# 20190105_ORIGAMI_V1-H-08slot-fixed.net
KiCad netlist of a schematic drawn in EAGLE
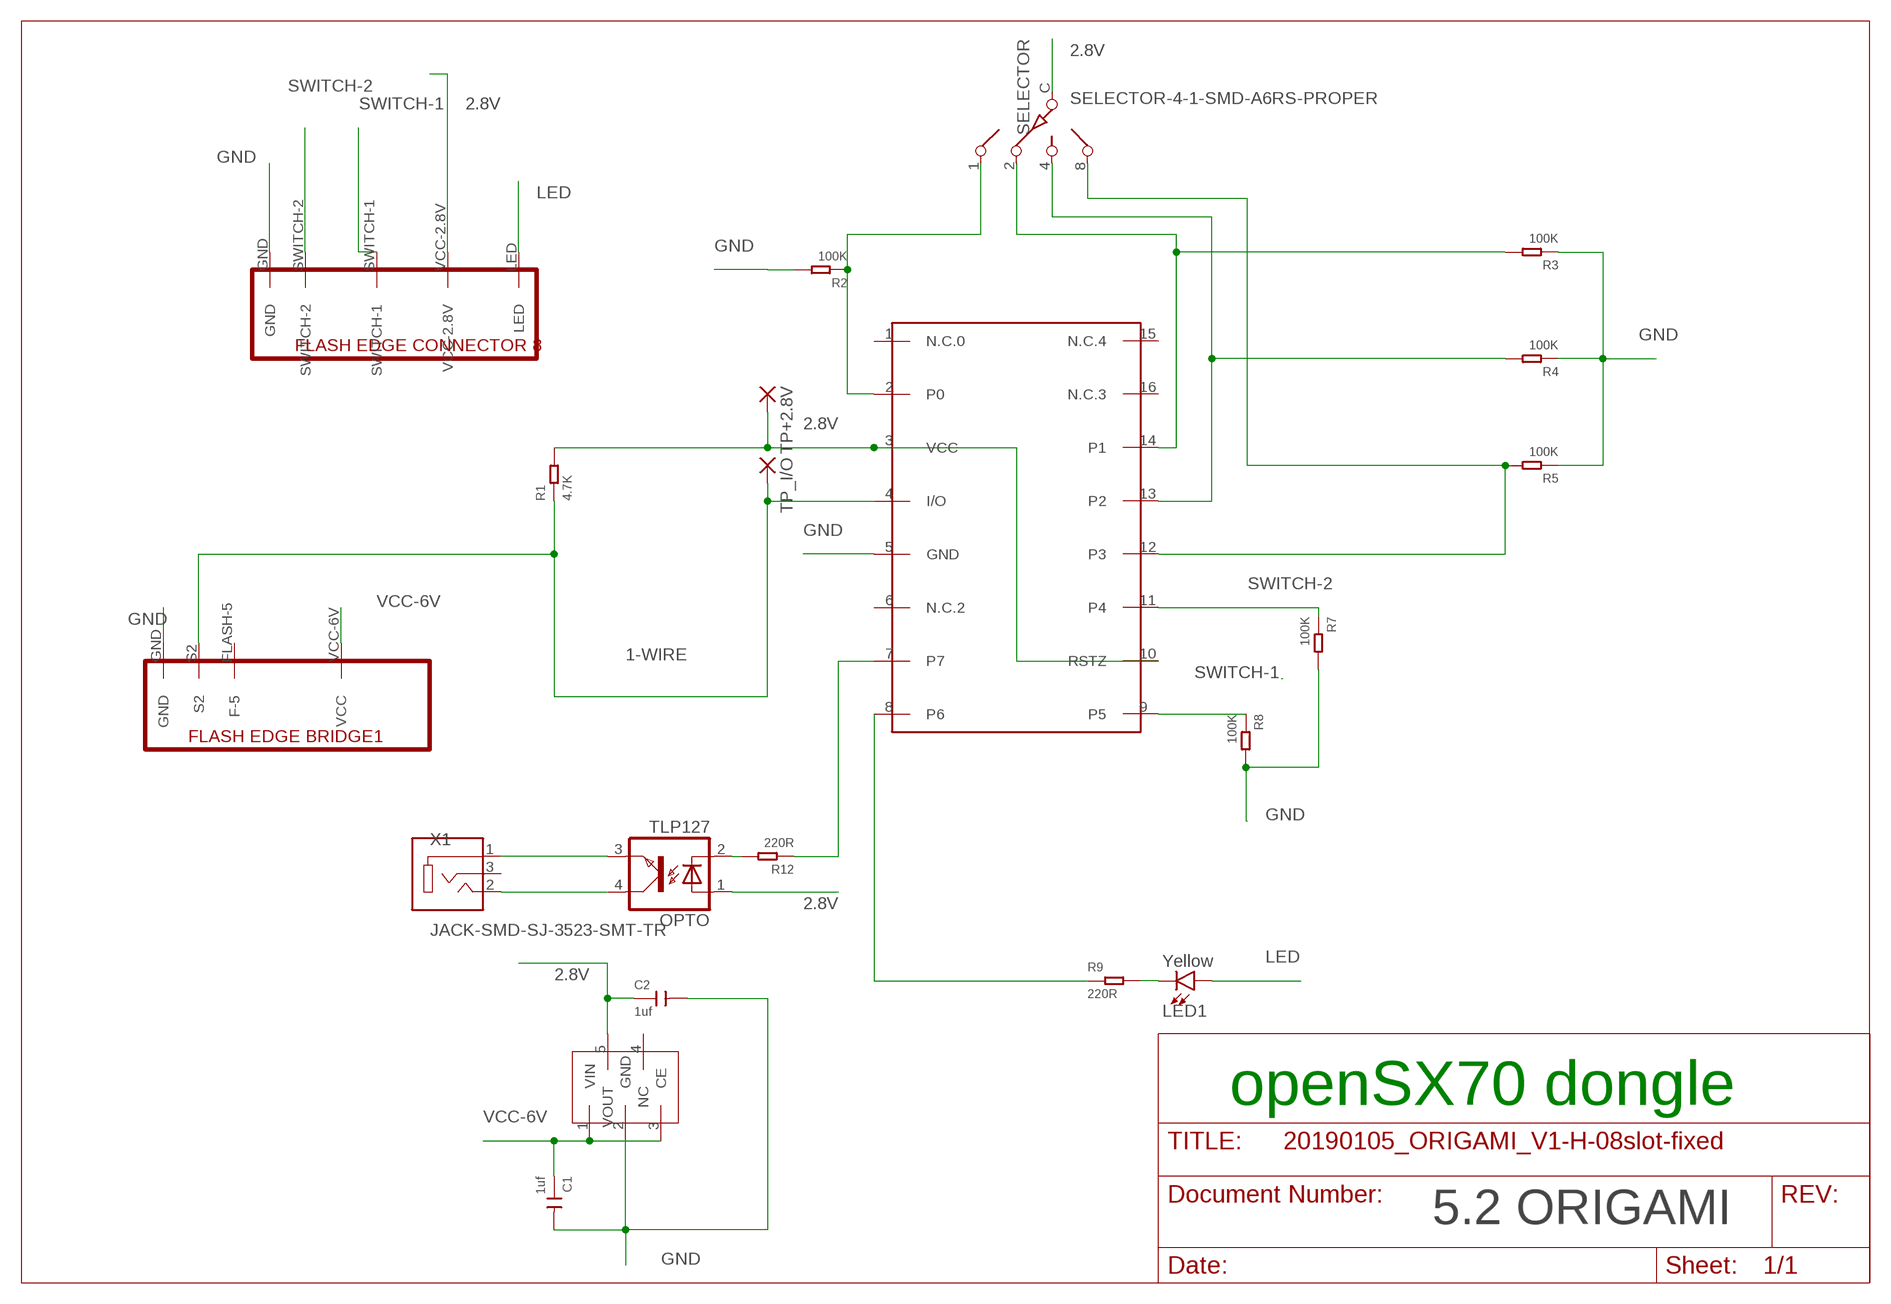
[diagram p0: schematic, sheet 1]

(export (version "E")
  (design (tool "Eeschema 10.0.6"))
  (components
    (comp (ref "C1")
      (value "1uf")
      (footprint "eagle-import:C0603")
      (fields (field (name "MPN") "CC0603KRX7R8BB105"))
      (libsource (lib "eagle-import") (part "CERAMIC-1UF-25V-10%-X7R(0603)"))
    )
    (comp (ref "C2")
      (value "1uf")
      (footprint "eagle-import:C0603")
      (fields (field (name "MPN") "CC0603KRX7R8BB105"))
      (libsource (lib "eagle-import") (part "CERAMIC-1UF-25V-10%-X7R(0603)"))
    )
    (comp (ref "DS2408")
      (value "DS2408")
      (footprint "eagle-import:SO16")
      (libsource (lib "eagle-import") (part "DS2408"))
    )
    (comp (ref "LED1")
      (value "Yellow")
      (footprint "eagle-import:LED-1206")
      (libsource (lib "eagle-import") (part "LED-YELLOWLILYPAD"))
    )
    (comp (ref "OPTO")
      (value "TLP127")
      (footprint "eagle-import:SO-4")
      (libsource (lib "eagle-import") (part "TLP127"))
    )
    (comp (ref "R1")
      (value "4.7K")
      (footprint "eagle-import:R0603")
      (fields (field (name "MPN") "RC0603JR-074K7L"))
      (libsource (lib "eagle-import") (part "SMD-RES-4.7K-5%-1/10W(0603)"))
    )
    (comp (ref "R2")
      (value "100K")
      (footprint "eagle-import:R0603")
      (fields (field (name "MPN") "RC0603FR-07100KL"))
      (libsource (lib "eagle-import") (part "SMD-RES-100K-1%-1/10W(0603)"))
    )
    (comp (ref "R3")
      (value "100K")
      (footprint "eagle-import:R0603")
      (fields (field (name "MPN") "RC0603FR-07100KL"))
      (libsource (lib "eagle-import") (part "SMD-RES-100K-1%-1/10W(0603)"))
    )
    (comp (ref "R4")
      (value "100K")
      (footprint "eagle-import:R0603")
      (fields (field (name "MPN") "RC0603FR-07100KL"))
      (libsource (lib "eagle-import") (part "SMD-RES-100K-1%-1/10W(0603)"))
    )
    (comp (ref "R5")
      (value "100K")
      (footprint "eagle-import:R0603")
      (fields (field (name "MPN") "RC0603FR-07100KL"))
      (libsource (lib "eagle-import") (part "SMD-RES-100K-1%-1/10W(0603)"))
    )
    (comp (ref "R7")
      (value "100K")
      (footprint "eagle-import:R0603")
      (fields (field (name "MPN") "RC0603FR-07100KL"))
      (libsource (lib "eagle-import") (part "SMD-RES-100K-1%-1/10W(0603)"))
    )
    (comp (ref "R8")
      (value "100K")
      (footprint "eagle-import:R0603")
      (fields (field (name "MPN") "RC0603FR-07100KL"))
      (libsource (lib "eagle-import") (part "SMD-RES-100K-1%-1/10W(0603)"))
    )
    (comp (ref "R9")
      (value "220R")
      (footprint "eagle-import:R0603")
      (fields (field (name "MPN") "RC0603JR-07220RL"))
      (libsource (lib "eagle-import") (part "SMD-RES-220R-5%-1/10W(0603)"))
    )
    (comp (ref "R12")
      (value "220R")
      (footprint "eagle-import:R0603")
      (fields (field (name "MPN") "RC0603JR-07220RL"))
      (libsource (lib "eagle-import") (part "SMD-RES-220R-5%-1/10W(0603)"))
    )
    (comp (ref "REG")
      (value "NCP4688")
      (footprint "eagle-import:SOT-23-5")
      (libsource (lib "eagle-import") (part "NCP4688"))
    )
    (comp (ref "SELECTOR")
      (value "SELECTOR-4-1-SMD-A6RS-PROPER")
      (footprint "eagle-import:A6RS-161RS")
      (libsource (lib "eagle-import") (part "SELECTOR-4-1-SMD-A6RS-PROPER"))
    )
    (comp (ref "TP+2.8V")
      (value "SMD2")
      (footprint "eagle-import:SMD1,27-2,54")
      (libsource (lib "eagle-import") (part "SMD2"))
    )
    (comp (ref "TP_I/O")
      (value "SMD2")
      (footprint "eagle-import:SMD1,27-2,54")
      (libsource (lib "eagle-import") (part "SMD2"))
    )
    (comp (ref "U$1")
      (value "FLASH-BRIDGE-SW1-SW2-LED")
      (footprint "eagle-import:FLASH-8-BRIDGE-SW1-SW2-LED")
      (libsource (lib "eagle-import") (part "FLASH-BRIDGE-SW1-SW2-LED"))
    )
    (comp (ref "U$2")
      (value "FLASH-BRIDGE1")
      (footprint "eagle-import:FLASH-8-BRIDGE1")
      (libsource (lib "eagle-import") (part "FLASH-BRIDGE1"))
    )
    (comp (ref "X1")
      (value "JACK-SMD-SJ-3523-SMT-TR")
      (footprint "eagle-import:CUI_SJ-3523-SMT-TR")
      (fields (field (name "MF") "CUI Inc.") (field (name "MP") "SJ-3523-SMT-TR"))
      (libsource (lib "eagle-import") (part "JACK-SMD-SJ-3523-SMT-TR"))
    )
  )
  (nets
    (net (code "1") (name "/1-WIRE") (class "Default")
      (node (ref "DS2408") (pin "4") (pinfunction "I/O_4") (pintype "bidirectional"))
      (node (ref "R1") (pin "1") (pinfunction "1_1") (pintype "passive"))
      (node (ref "TP_I/O") (pin "1") (pinfunction "P_1") (pintype "passive"))
      (node (ref "U$2") (pin "S2") (pinfunction "S2_S2") (pintype "bidirectional"))
    )
    (net (code "2") (name "/2.8V") (class "Default")
      (node (ref "C2") (pin "1") (pinfunction "1_1") (pintype "passive"))
      (node (ref "DS2408") (pin "10") (pinfunction "RSTZ_10") (pintype "bidirectional"))
      (node (ref "DS2408") (pin "3") (pinfunction "VCC_3") (pintype "bidirectional"))
      (node (ref "OPTO") (pin "1") (pinfunction "A_1") (pintype "passive"))
      (node (ref "R1") (pin "2") (pinfunction "2_2") (pintype "passive"))
      (node (ref "REG") (pin "5") (pinfunction "VOUT_5") (pintype "bidirectional"))
      (node (ref "SELECTOR") (pin "C") (pinfunction "C_C") (pintype "passive"))
      (node (ref "TP+2.8V") (pin "1") (pinfunction "P_1") (pintype "passive"))
      (node (ref "U$1") (pin "VCC-2.8V") (pinfunction "VCC-2.8V_VCC-2.8V") (pintype "bidirectional"))
    )
    (net (code "3") (name "/GND") (class "Default")
      (node (ref "C1") (pin "2") (pinfunction "2_2") (pintype "passive"))
      (node (ref "C2") (pin "2") (pinfunction "2_2") (pintype "passive"))
      (node (ref "DS2408") (pin "5") (pinfunction "GND_5") (pintype "bidirectional"))
      (node (ref "R2") (pin "2") (pinfunction "2_2") (pintype "passive"))
      (node (ref "R3") (pin "1") (pinfunction "1_1") (pintype "passive"))
      (node (ref "R4") (pin "1") (pinfunction "1_1") (pintype "passive"))
      (node (ref "R5") (pin "1") (pinfunction "1_1") (pintype "passive"))
      (node (ref "R7") (pin "2") (pinfunction "2_2") (pintype "passive"))
      (node (ref "R8") (pin "2") (pinfunction "2_2") (pintype "passive"))
      (node (ref "REG") (pin "2") (pinfunction "GND_2") (pintype "bidirectional"))
      (node (ref "U$1") (pin "GND") (pinfunction "GND_GND") (pintype "bidirectional"))
      (node (ref "U$2") (pin "GND") (pinfunction "GND_GND") (pintype "bidirectional"))
    )
    (net (code "4") (name "/LED") (class "Default")
      (node (ref "LED1") (pin "A") (pinfunction "A_A") (pintype "passive"))
      (node (ref "U$1") (pin "LED") (pinfunction "LED_LED") (pintype "bidirectional"))
    )
    (net (code "5") (name "/SWITCH-1") (class "Default")
      (node (ref "DS2408") (pin "9") (pinfunction "P5_9") (pintype "bidirectional"))
      (node (ref "R8") (pin "1") (pinfunction "1_1") (pintype "passive"))
      (node (ref "U$1") (pin "SWITCH-1") (pinfunction "SWITCH-1_SWITCH-1") (pintype "bidirectional"))
    )
    (net (code "6") (name "/SWITCH-2") (class "Default")
      (node (ref "DS2408") (pin "11") (pinfunction "P4_11") (pintype "bidirectional"))
      (node (ref "R7") (pin "1") (pinfunction "1_1") (pintype "passive"))
      (node (ref "U$1") (pin "SWITCH-2") (pinfunction "SWITCH-2_SWITCH-2") (pintype "bidirectional"))
    )
    (net (code "7") (name "/VCC-6V") (class "Default")
      (node (ref "C1") (pin "1") (pinfunction "1_1") (pintype "passive"))
      (node (ref "REG") (pin "1") (pinfunction "VIN_1") (pintype "bidirectional"))
      (node (ref "REG") (pin "3") (pinfunction "CE_3") (pintype "bidirectional"))
      (node (ref "U$2") (pin "VCC-6V") (pinfunction "VCC_VCC-6V") (pintype "bidirectional"))
    )
    (net (code "8") (name "Net-(DS2408-P0)") (class "Default")
      (node (ref "DS2408") (pin "2") (pinfunction "P0_2") (pintype "bidirectional"))
      (node (ref "R2") (pin "1") (pinfunction "1_1") (pintype "passive"))
      (node (ref "SELECTOR") (pin "1") (pinfunction "8_1") (pintype "passive"))
    )
    (net (code "9") (name "Net-(DS2408-P1)") (class "Default")
      (node (ref "DS2408") (pin "14") (pinfunction "P1_14") (pintype "bidirectional"))
      (node (ref "R3") (pin "2") (pinfunction "2_2") (pintype "passive"))
      (node (ref "SELECTOR") (pin "2") (pinfunction "4_2") (pintype "passive"))
    )
    (net (code "10") (name "Net-(DS2408-P2)") (class "Default")
      (node (ref "DS2408") (pin "13") (pinfunction "P2_13") (pintype "bidirectional"))
      (node (ref "R4") (pin "2") (pinfunction "2_2") (pintype "passive"))
      (node (ref "SELECTOR") (pin "4") (pinfunction "2_4") (pintype "passive"))
    )
    (net (code "11") (name "Net-(DS2408-P3)") (class "Default")
      (node (ref "DS2408") (pin "12") (pinfunction "P3_12") (pintype "bidirectional"))
      (node (ref "R5") (pin "2") (pinfunction "2_2") (pintype "passive"))
      (node (ref "SELECTOR") (pin "8") (pinfunction "1_8") (pintype "passive"))
    )
    (net (code "12") (name "Net-(DS2408-P6)") (class "Default")
      (node (ref "DS2408") (pin "8") (pinfunction "P6_8") (pintype "bidirectional"))
      (node (ref "R9") (pin "1") (pinfunction "1_1") (pintype "passive"))
    )
    (net (code "13") (name "Net-(DS2408-P7)") (class "Default")
      (node (ref "DS2408") (pin "7") (pinfunction "P7_7") (pintype "bidirectional"))
      (node (ref "R12") (pin "1") (pinfunction "1_1") (pintype "passive"))
    )
    (net (code "14") (name "Net-(LED1-PadC)") (class "Default")
      (node (ref "LED1") (pin "C") (pinfunction "C_C") (pintype "passive"))
      (node (ref "R9") (pin "2") (pinfunction "2_2") (pintype "passive"))
    )
    (net (code "15") (name "Net-(OPTO-C)") (class "Default")
      (node (ref "OPTO") (pin "2") (pinfunction "C_2") (pintype "passive"))
      (node (ref "R12") (pin "2") (pinfunction "2_2") (pintype "passive"))
    )
    (net (code "16") (name "Net-(OPTO-COL)") (class "Default")
      (node (ref "OPTO") (pin "4") (pinfunction "COL_4") (pintype "passive"))
      (node (ref "X1") (pin "2") (pinfunction "2_2") (pintype "passive"))
    )
    (net (code "17") (name "Net-(OPTO-EMIT)") (class "Default")
      (node (ref "OPTO") (pin "3") (pinfunction "EMIT_3") (pintype "passive"))
      (node (ref "X1") (pin "1") (pinfunction "1_1") (pintype "passive"))
    )
    (net (code "18") (name "unconnected-(DS2408-N.C.0-Pad1)") (class "Default")
      (node (ref "DS2408") (pin "1") (pinfunction "N.C.0_1") (pintype "bidirectional"))
    )
    (net (code "19") (name "unconnected-(DS2408-N.C.2-Pad6)") (class "Default")
      (node (ref "DS2408") (pin "6") (pinfunction "N.C.2_6") (pintype "bidirectional"))
    )
    (net (code "20") (name "unconnected-(DS2408-N.C.3-Pad16)") (class "Default")
      (node (ref "DS2408") (pin "16") (pinfunction "N.C.3_16") (pintype "bidirectional"))
    )
    (net (code "21") (name "unconnected-(DS2408-N.C.4-Pad15)") (class "Default")
      (node (ref "DS2408") (pin "15") (pinfunction "N.C.4_15") (pintype "bidirectional"))
    )
    (net (code "22") (name "unconnected-(REG-NC-Pad4)") (class "Default")
      (node (ref "REG") (pin "4") (pinfunction "NC_4") (pintype "bidirectional"))
    )
    (net (code "23") (name "unconnected-(U$2-F-5-PadFLASH-5)") (class "Default")
      (node (ref "U$2") (pin "FLASH-5") (pinfunction "F-5_FLASH-5") (pintype "bidirectional"))
    )
    (net (code "24") (name "unconnected-(X1-Pad3)") (class "Default")
      (node (ref "X1") (pin "3") (pinfunction "3_3") (pintype "passive"))
    )
  )
)
